# DAC_40MHz.net
KiCad netlist of a schematic drawn in Altium Designer
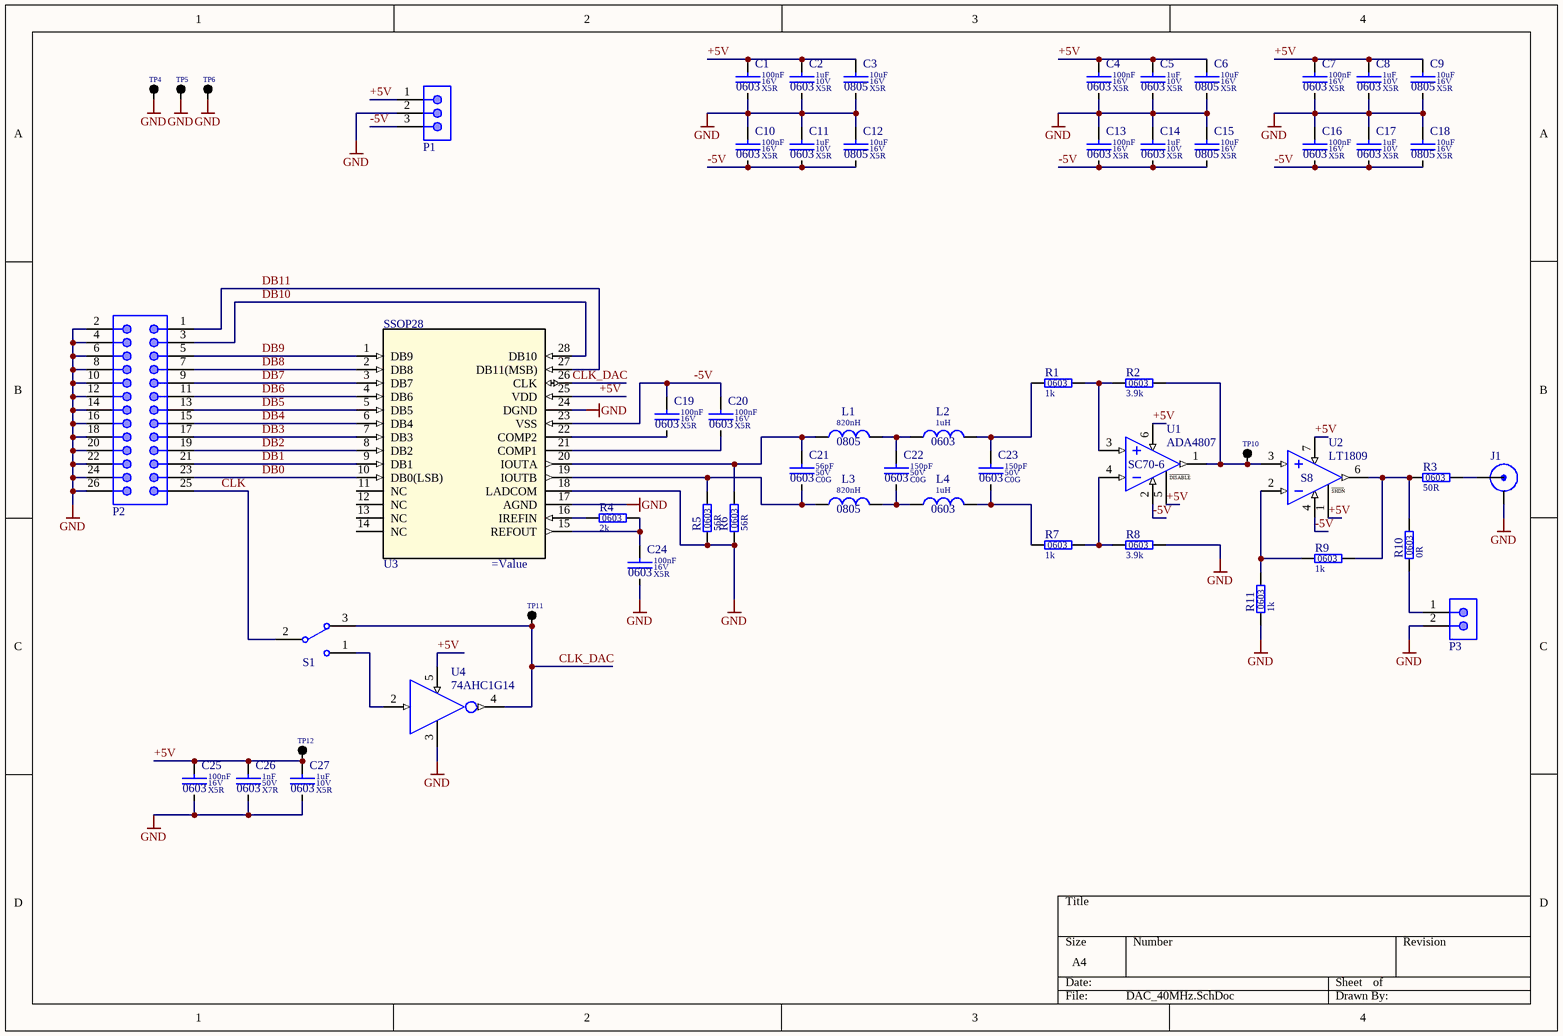
[diagram p0: DAC_40MHz.SchDoc]

(export (version "E")
  (design (tool "Eeschema 10.0.6"))
  (components
    (comp (ref "C1")
      (value "100nF")
      (footprint "C_0603")
      (description "Capacitor")
      (fields
        (field (name "DIELECTRIC") "X5R")
        (field (name "VOLTAGE") "16V")
        (field (name "SCH_FOOTPRINT") "0603")
        (field (name "PART NUMBER") "C_100nF_16V_X5R_0603_10")
        (field (name "TOLERANCE") "10%")
      )
      (libsource (lib "MatyczLib") (part "C"))
    )
    (comp (ref "C2")
      (value "1uF")
      (footprint "C_0603")
      (description "Capacitor")
      (fields
        (field (name "DIELECTRIC") "X5R")
        (field (name "VOLTAGE") "10V")
        (field (name "SCH_FOOTPRINT") "0603")
        (field (name "PART NUMBER") "C_1uF_10V_X5R_0603_10")
        (field (name "TOLERANCE") "10%")
      )
      (libsource (lib "MatyczLib") (part "C"))
    )
    (comp (ref "C3")
      (value "10uF")
      (footprint "C_0805")
      (description "Capacitor")
      (fields
        (field (name "DIELECTRIC") "X5R")
        (field (name "VOLTAGE") "16V")
        (field (name "SCH_FOOTPRINT") "0805")
        (field (name "PART NUMBER") "C_10uF_16V_X5R_0805_10")
        (field (name "TOLERANCE") "10%")
      )
      (libsource (lib "MatyczLib") (part "C"))
    )
    (comp (ref "C4")
      (value "100nF")
      (footprint "C_0603")
      (description "Capacitor")
      (fields
        (field (name "DIELECTRIC") "X5R")
        (field (name "VOLTAGE") "16V")
        (field (name "SCH_FOOTPRINT") "0603")
        (field (name "PART NUMBER") "C_100nF_16V_X5R_0603_10")
        (field (name "TOLERANCE") "10%")
      )
      (libsource (lib "MatyczLib") (part "C"))
    )
    (comp (ref "C5")
      (value "1uF")
      (footprint "C_0603")
      (description "Capacitor")
      (fields
        (field (name "DIELECTRIC") "X5R")
        (field (name "VOLTAGE") "10V")
        (field (name "SCH_FOOTPRINT") "0603")
        (field (name "PART NUMBER") "C_1uF_10V_X5R_0603_10")
        (field (name "TOLERANCE") "10%")
      )
      (libsource (lib "MatyczLib") (part "C"))
    )
    (comp (ref "C6")
      (value "10uF")
      (footprint "C_0805")
      (description "Capacitor")
      (fields
        (field (name "DIELECTRIC") "X5R")
        (field (name "VOLTAGE") "16V")
        (field (name "SCH_FOOTPRINT") "0805")
        (field (name "PART NUMBER") "C_10uF_16V_X5R_0805_10")
        (field (name "TOLERANCE") "10%")
      )
      (libsource (lib "MatyczLib") (part "C"))
    )
    (comp (ref "C7")
      (value "100nF")
      (footprint "C_0603")
      (description "Capacitor")
      (fields
        (field (name "DIELECTRIC") "X5R")
        (field (name "VOLTAGE") "16V")
        (field (name "SCH_FOOTPRINT") "0603")
        (field (name "PART NUMBER") "C_100nF_16V_X5R_0603_10")
        (field (name "TOLERANCE") "10%")
      )
      (libsource (lib "MatyczLib") (part "C"))
    )
    (comp (ref "C8")
      (value "1uF")
      (footprint "C_0603")
      (description "Capacitor")
      (fields
        (field (name "DIELECTRIC") "X5R")
        (field (name "VOLTAGE") "10V")
        (field (name "SCH_FOOTPRINT") "0603")
        (field (name "PART NUMBER") "C_1uF_10V_X5R_0603_10")
        (field (name "TOLERANCE") "10%")
      )
      (libsource (lib "MatyczLib") (part "C"))
    )
    (comp (ref "C9")
      (value "10uF")
      (footprint "C_0805")
      (description "Capacitor")
      (fields
        (field (name "DIELECTRIC") "X5R")
        (field (name "VOLTAGE") "16V")
        (field (name "SCH_FOOTPRINT") "0805")
        (field (name "PART NUMBER") "C_10uF_16V_X5R_0805_10")
        (field (name "TOLERANCE") "10%")
      )
      (libsource (lib "MatyczLib") (part "C"))
    )
    (comp (ref "C10")
      (value "100nF")
      (footprint "C_0603")
      (description "Capacitor")
      (fields
        (field (name "DIELECTRIC") "X5R")
        (field (name "VOLTAGE") "16V")
        (field (name "SCH_FOOTPRINT") "0603")
        (field (name "PART NUMBER") "C_100nF_16V_X5R_0603_10")
        (field (name "TOLERANCE") "10%")
      )
      (libsource (lib "MatyczLib") (part "C"))
    )
    (comp (ref "C11")
      (value "1uF")
      (footprint "C_0603")
      (description "Capacitor")
      (fields
        (field (name "DIELECTRIC") "X5R")
        (field (name "VOLTAGE") "10V")
        (field (name "SCH_FOOTPRINT") "0603")
        (field (name "PART NUMBER") "C_1uF_10V_X5R_0603_10")
        (field (name "TOLERANCE") "10%")
      )
      (libsource (lib "MatyczLib") (part "C"))
    )
    (comp (ref "C12")
      (value "10uF")
      (footprint "C_0805")
      (description "Capacitor")
      (fields
        (field (name "DIELECTRIC") "X5R")
        (field (name "VOLTAGE") "16V")
        (field (name "SCH_FOOTPRINT") "0805")
        (field (name "PART NUMBER") "C_10uF_16V_X5R_0805_10")
        (field (name "TOLERANCE") "10%")
      )
      (libsource (lib "MatyczLib") (part "C"))
    )
    (comp (ref "C13")
      (value "100nF")
      (footprint "C_0603")
      (description "Capacitor")
      (fields
        (field (name "DIELECTRIC") "X5R")
        (field (name "VOLTAGE") "16V")
        (field (name "SCH_FOOTPRINT") "0603")
        (field (name "PART NUMBER") "C_100nF_16V_X5R_0603_10")
        (field (name "TOLERANCE") "10%")
      )
      (libsource (lib "MatyczLib") (part "C"))
    )
    (comp (ref "C14")
      (value "1uF")
      (footprint "C_0603")
      (description "Capacitor")
      (fields
        (field (name "DIELECTRIC") "X5R")
        (field (name "VOLTAGE") "10V")
        (field (name "SCH_FOOTPRINT") "0603")
        (field (name "PART NUMBER") "C_1uF_10V_X5R_0603_10")
        (field (name "TOLERANCE") "10%")
      )
      (libsource (lib "MatyczLib") (part "C"))
    )
    (comp (ref "C15")
      (value "10uF")
      (footprint "C_0805")
      (description "Capacitor")
      (fields
        (field (name "DIELECTRIC") "X5R")
        (field (name "VOLTAGE") "16V")
        (field (name "SCH_FOOTPRINT") "0805")
        (field (name "PART NUMBER") "C_10uF_16V_X5R_0805_10")
        (field (name "TOLERANCE") "10%")
      )
      (libsource (lib "MatyczLib") (part "C"))
    )
    (comp (ref "C16")
      (value "100nF")
      (footprint "C_0603")
      (description "Capacitor")
      (fields
        (field (name "DIELECTRIC") "X5R")
        (field (name "VOLTAGE") "16V")
        (field (name "SCH_FOOTPRINT") "0603")
        (field (name "PART NUMBER") "C_100nF_16V_X5R_0603_10")
        (field (name "TOLERANCE") "10%")
      )
      (libsource (lib "MatyczLib") (part "C"))
    )
    (comp (ref "C17")
      (value "1uF")
      (footprint "C_0603")
      (description "Capacitor")
      (fields
        (field (name "DIELECTRIC") "X5R")
        (field (name "VOLTAGE") "10V")
        (field (name "SCH_FOOTPRINT") "0603")
        (field (name "PART NUMBER") "C_1uF_10V_X5R_0603_10")
        (field (name "TOLERANCE") "10%")
      )
      (libsource (lib "MatyczLib") (part "C"))
    )
    (comp (ref "C18")
      (value "10uF")
      (footprint "C_0805")
      (description "Capacitor")
      (fields
        (field (name "DIELECTRIC") "X5R")
        (field (name "VOLTAGE") "16V")
        (field (name "SCH_FOOTPRINT") "0805")
        (field (name "PART NUMBER") "C_10uF_16V_X5R_0805_10")
        (field (name "TOLERANCE") "10%")
      )
      (libsource (lib "MatyczLib") (part "C"))
    )
    (comp (ref "C19")
      (value "100nF")
      (footprint "C_0603")
      (description "Capacitor")
      (fields
        (field (name "DIELECTRIC") "X5R")
        (field (name "VOLTAGE") "16V")
        (field (name "SCH_FOOTPRINT") "0603")
        (field (name "PART NUMBER") "C_100nF_16V_X5R_0603_10")
        (field (name "TOLERANCE") "10%")
      )
      (libsource (lib "MatyczLib") (part "C"))
    )
    (comp (ref "C20")
      (value "100nF")
      (footprint "C_0603")
      (description "Capacitor")
      (fields
        (field (name "DIELECTRIC") "X5R")
        (field (name "VOLTAGE") "16V")
        (field (name "SCH_FOOTPRINT") "0603")
        (field (name "PART NUMBER") "C_100nF_16V_X5R_0603_10")
        (field (name "TOLERANCE") "10%")
      )
      (libsource (lib "MatyczLib") (part "C"))
    )
    (comp (ref "C21")
      (value "56pF")
      (footprint "C_0603")
      (description "Capacitor")
      (fields
        (field (name "DIELECTRIC") "C0G")
        (field (name "VOLTAGE") "50V")
        (field (name "SCH_FOOTPRINT") "0603")
        (field (name "PART NUMBER") "C_56pF_50V_C0G_0603_5")
        (field (name "TOLERANCE") "5%")
      )
      (libsource (lib "MatyczLib") (part "C"))
    )
    (comp (ref "C22")
      (value "150pF")
      (footprint "C_0603")
      (description "Capacitor")
      (fields
        (field (name "DIELECTRIC") "C0G")
        (field (name "VOLTAGE") "50V")
        (field (name "SCH_FOOTPRINT") "0603")
        (field (name "PART NUMBER") "C_150pF_50V_C0G_0603_5")
        (field (name "TOLERANCE") "5%")
      )
      (libsource (lib "MatyczLib") (part "C"))
    )
    (comp (ref "C23")
      (value "150pF")
      (footprint "C_0603")
      (description "Capacitor")
      (fields
        (field (name "DIELECTRIC") "C0G")
        (field (name "VOLTAGE") "50V")
        (field (name "SCH_FOOTPRINT") "0603")
        (field (name "PART NUMBER") "C_150pF_50V_C0G_0603_5")
        (field (name "TOLERANCE") "5%")
      )
      (libsource (lib "MatyczLib") (part "C"))
    )
    (comp (ref "C24")
      (value "100nF")
      (footprint "C_0603")
      (description "Capacitor")
      (fields
        (field (name "DIELECTRIC") "X5R")
        (field (name "VOLTAGE") "16V")
        (field (name "SCH_FOOTPRINT") "0603")
        (field (name "PART NUMBER") "C_100nF_16V_X5R_0603_10")
        (field (name "TOLERANCE") "10%")
      )
      (libsource (lib "MatyczLib") (part "C"))
    )
    (comp (ref "C25")
      (value "100nF")
      (footprint "C_0603")
      (description "Capacitor")
      (fields
        (field (name "DIELECTRIC") "X5R")
        (field (name "VOLTAGE") "16V")
        (field (name "SCH_FOOTPRINT") "0603")
        (field (name "PART NUMBER") "C_100nF_16V_X5R_0603_10")
        (field (name "TOLERANCE") "10%")
      )
      (libsource (lib "MatyczLib") (part "C"))
    )
    (comp (ref "C26")
      (value "1nF")
      (footprint "C_0603")
      (description "Capacitor")
      (fields
        (field (name "DIELECTRIC") "X7R")
        (field (name "VOLTAGE") "50V")
        (field (name "SCH_FOOTPRINT") "0603")
        (field (name "PART NUMBER") "C_1nF_50V_X7R_0603_10")
        (field (name "TOLERANCE") "10%")
      )
      (libsource (lib "MatyczLib") (part "C"))
    )
    (comp (ref "C27")
      (value "1uF")
      (footprint "C_0603")
      (description "Capacitor")
      (fields
        (field (name "DIELECTRIC") "X5R")
        (field (name "VOLTAGE") "10V")
        (field (name "SCH_FOOTPRINT") "0603")
        (field (name "PART NUMBER") "C_1uF_10V_X5R_0603_10")
        (field (name "TOLERANCE") "10%")
      )
      (libsource (lib "MatyczLib") (part "C"))
    )
    (comp (ref "J1")
      (value "SMA vertical connector")
      (footprint "J_SMA_VERTICAL")
      (fields (field (name "PART NUMBER") "J_SMA_VERTICAL"))
      (libsource (lib "MatyczLib") (part "J_SMA_VERTICAL"))
    )
    (comp (ref "L1")
      (value "820nH")
      (footprint "L_0805")
      (description "Induction")
      (fields
        (field (name "SCH_FOOTPRINT") "0805")
        (field (name "PART NUMBER") "L_820nH_180mA_0805")
        (field (name "MANUFACTURER") "MULTICOMP")
      )
      (libsource (lib "MatyczLib") (part "L"))
    )
    (comp (ref "L2")
      (value "1uH")
      (footprint "L_0603")
      (description "Induction")
      (fields
        (field (name "SCH_FOOTPRINT") "0603")
        (field (name "PART NUMBER") "L_1uH_100mA_0603")
        (field (name "MANUFACTURER") "BOURNS")
      )
      (libsource (lib "MatyczLib") (part "L"))
    )
    (comp (ref "L3")
      (value "820nH")
      (footprint "L_0805")
      (description "Induction")
      (fields
        (field (name "SCH_FOOTPRINT") "0805")
        (field (name "PART NUMBER") "L_820nH_180mA_0805")
        (field (name "MANUFACTURER") "MULTICOMP")
      )
      (libsource (lib "MatyczLib") (part "L"))
    )
    (comp (ref "L4")
      (value "1uH")
      (footprint "L_0603")
      (description "Induction")
      (fields
        (field (name "SCH_FOOTPRINT") "0603")
        (field (name "PART NUMBER") "L_1uH_100mA_0603")
        (field (name "MANUFACTURER") "BOURNS")
      )
      (libsource (lib "MatyczLib") (part "L"))
    )
    (comp (ref "P1")
      (value "Header 1x3, THT, 2,54mm")
      (footprint "P_HEADER_1x3_THT_2.54_VERT")
      (description "Pin Header, THT, pitch 2.54mm, Single Row, Vertical, 3pin")
      (fields (field (name "PART NUMBER") "P_HEADER_1x3_THT_2.54_VERT"))
      (libsource (lib "MatyczLib") (part "P_HEADER_1x3_THT_2.54_VERT"))
    )
    (comp (ref "P2")
      (value "Header 2x13, THT, 2,54mm")
      (footprint "P_HEADER_2x13_THT_2.54_VERT")
      (description "Pin Header, THT, pitch 2.54mm, Dual Row, Vertical, 26pin")
      (fields (field (name "PART NUMBER") "P_HEADER_2x13_THT_2.54_VERT"))
      (libsource (lib "MatyczLib") (part "P_HEADER_2x13_THT_2.54_VERT"))
    )
    (comp (ref "P3")
      (value "Header 1x2, THT, 2,54mm")
      (footprint "P_HEADER_1x2_THT_2.54_VERT")
      (description "Pin Header, THT, pitch 2.54mm, Single Row, Vertical, 2pin")
      (fields (field (name "PART NUMBER") "P_HEADER_1x2_THT_2.54_VERT"))
      (libsource (lib "MatyczLib") (part "P_HEADER_1x2_THT_2.54_VERT"))
    )
    (comp (ref "R1")
      (value "1k")
      (footprint "R_0603")
      (fields
        (field (name "SCH_FOOTPRINT") "0603")
        (field (name "PART NUMBER") "R_1k_0603_1")
        (field (name "TOLERANCE") "1%")
        (field (name "POWER") "100mW")
      )
      (libsource (lib "MatyczLib") (part "R"))
    )
    (comp (ref "R2")
      (value "3.9k")
      (footprint "R_0603")
      (fields
        (field (name "SCH_FOOTPRINT") "0603")
        (field (name "PART NUMBER") "R_3.9k_0603_1")
        (field (name "TOLERANCE") "1%")
        (field (name "POWER") "100mW")
      )
      (libsource (lib "MatyczLib") (part "R"))
    )
    (comp (ref "R3")
      (value "50R")
      (footprint "R_0603")
      (fields
        (field (name "SCH_FOOTPRINT") "0603")
        (field (name "PART NUMBER") "R_50R_0603_1")
        (field (name "TOLERANCE") "1%")
        (field (name "POWER") "100mW")
      )
      (libsource (lib "MatyczLib") (part "R"))
    )
    (comp (ref "R4")
      (value "2k")
      (footprint "R_0603")
      (fields
        (field (name "SCH_FOOTPRINT") "0603")
        (field (name "PART NUMBER") "R_2k_0603_1")
        (field (name "TOLERANCE") "1%")
        (field (name "POWER") "100mW")
      )
      (libsource (lib "MatyczLib") (part "R"))
    )
    (comp (ref "R5")
      (value "56R")
      (footprint "R_0603")
      (fields
        (field (name "SCH_FOOTPRINT") "0603")
        (field (name "PART NUMBER") "R_56R_0603_1")
        (field (name "TOLERANCE") "1%")
        (field (name "POWER") "100mW")
      )
      (libsource (lib "") (part "R_1"))
    )
    (comp (ref "R6")
      (value "56R")
      (footprint "R_0603")
      (fields
        (field (name "SCH_FOOTPRINT") "0603")
        (field (name "PART NUMBER") "R_56R_0603_1")
        (field (name "TOLERANCE") "1%")
        (field (name "POWER") "100mW")
      )
      (libsource (lib "") (part "R_1"))
    )
    (comp (ref "R7")
      (value "1k")
      (footprint "R_0603")
      (fields
        (field (name "SCH_FOOTPRINT") "0603")
        (field (name "PART NUMBER") "R_1k_0603_1")
        (field (name "TOLERANCE") "1%")
        (field (name "POWER") "100mW")
      )
      (libsource (lib "MatyczLib") (part "R"))
    )
    (comp (ref "R8")
      (value "3.9k")
      (footprint "R_0603")
      (fields
        (field (name "SCH_FOOTPRINT") "0603")
        (field (name "PART NUMBER") "R_3.9k_0603_1")
        (field (name "TOLERANCE") "1%")
        (field (name "POWER") "100mW")
      )
      (libsource (lib "MatyczLib") (part "R"))
    )
    (comp (ref "R9")
      (value "1k")
      (footprint "R_0603")
      (fields
        (field (name "SCH_FOOTPRINT") "0603")
        (field (name "PART NUMBER") "R_1k_0603_1")
        (field (name "TOLERANCE") "1%")
        (field (name "POWER") "100mW")
      )
      (libsource (lib "MatyczLib") (part "R"))
    )
    (comp (ref "R10")
      (value "0R")
      (footprint "R_0603")
      (fields
        (field (name "SCH_FOOTPRINT") "0603")
        (field (name "PART NUMBER") "R_0R_0603_1")
        (field (name "TOLERANCE") "1%")
        (field (name "POWER") "100mW")
      )
      (libsource (lib "") (part "R_1"))
    )
    (comp (ref "R11")
      (value "1k")
      (footprint "R_0603")
      (fields
        (field (name "SCH_FOOTPRINT") "0603")
        (field (name "PART NUMBER") "R_1k_0603_1")
        (field (name "TOLERANCE") "1%")
        (field (name "POWER") "100mW")
      )
      (libsource (lib "") (part "R_1"))
    )
    (comp (ref "S1")
      (value "Single Pole Double Throw Slideswitch")
      (footprint "S_SLIDESWITCH_SPDT")
      (fields
        (field (name "PART NUMBER") "S_SLIDESWITCH_SPDT_OS102011MS2QN1")
        (field (name "MANUFACTURER PART NUMBER") "OS102011MS2QN13")
      )
      (libsource (lib "MatyczLib") (part "S_SPDT"))
    )
    (comp (ref "TP4")
      (value "Single pin")
      (footprint "TP_1PIN")
      (description "Testpoint")
      (fields (field (name "PART NUMBER") "TP_1PIN"))
      (libsource (lib "Library") (part "TP_TESTPOINT"))
    )
    (comp (ref "TP5")
      (value "Single pin")
      (footprint "TP_1PIN")
      (description "Testpoint")
      (fields (field (name "PART NUMBER") "TP_1PIN"))
      (libsource (lib "Library") (part "TP_TESTPOINT"))
    )
    (comp (ref "TP6")
      (value "Single pin")
      (footprint "TP_1PIN")
      (description "Testpoint")
      (fields (field (name "PART NUMBER") "TP_1PIN"))
      (libsource (lib "Library") (part "TP_TESTPOINT"))
    )
    (comp (ref "TP10")
      (value "Single pin")
      (footprint "TP_1PIN")
      (description "Testpoint")
      (fields (field (name "PART NUMBER") "TP_1PIN"))
      (libsource (lib "Library") (part "TP_TESTPOINT"))
    )
    (comp (ref "TP11")
      (value "Single pin")
      (footprint "TP_1PIN")
      (description "Testpoint")
      (fields (field (name "PART NUMBER") "TP_1PIN"))
      (libsource (lib "Library") (part "TP_TESTPOINT"))
    )
    (comp (ref "TP12")
      (value "Single pin")
      (footprint "TP_1PIN")
      (description "Testpoint")
      (fields (field (name "PART NUMBER") "TP_1PIN"))
      (libsource (lib "Library") (part "TP_TESTPOINT"))
    )
    (comp (ref "U1")
      (value "ADA4807")
      (footprint "SC70-6_TSSOP6_2X1.25_MD")
      (fields
        (field (name "SCH_FOOTPRINT") "SC70-6")
        (field (name "PART NUMBER") "U_ADA4807-1AKSZ-R2")
        (field (name "MANUFACTURER") "ANALOG DEVICES")
      )
      (libsource (lib "MatyczLib") (part "U_ADA4807"))
    )
    (comp (ref "U2")
      (value "LT1809")
      (footprint "S8_SOP8_SOIC8_SO8_4.9X3.9_MD")
      (fields
        (field (name "SCH_FOOTPRINT") "S8")
        (field (name "PART NUMBER") "U_LT1809CS8")
        (field (name "MANUFACTURER") "ANALOG DEVICES")
      )
      (libsource (lib "MatyczLib") (part "U_LT1809"))
    )
    (comp (ref "U3")
      (value "~")
      (footprint "SSOP28_SOP28_SO28_SOIC8_10.2X5.29_MD")
      (description "12-bit 50Msps DAC")
      (fields
        (field (name "SCH_FOOTPRINT") "SSOP28")
        (field (name "PART NUMBER") "U_LTC1666")
        (field (name "MANUFACTURER PART NUMBER") "LTC1666")
      )
      (libsource (lib "MatyczLib") (part "U_LTC1666"))
    )
    (comp (ref "U4")
      (value "74AHC1G14")
      (footprint "SOT23-5_2.05X2.13_MD")
      (description "Inverting Schmitt trigger")
      (fields (field (name "PART NUMBER") "U_74AHC1G14") (field (name "MANUFACTURER") "NEXPERIA"))
      (libsource (lib "MatyczLib") (part "U_SCHMITT_INVERTER"))
    )
  )
  (nets
    (net (code "1") (name "/+5V") (class "Default")
      (node (ref "C1") (pin "1") (pinfunction "1_1") (pintype "passive"))
      (node (ref "C2") (pin "1") (pinfunction "1_1") (pintype "passive"))
      (node (ref "C25") (pin "1") (pinfunction "1_1") (pintype "passive"))
      (node (ref "C26") (pin "1") (pinfunction "1_1") (pintype "passive"))
      (node (ref "C27") (pin "1") (pinfunction "1_1") (pintype "passive"))
      (node (ref "C3") (pin "1") (pinfunction "1_1") (pintype "passive"))
      (node (ref "C4") (pin "1") (pinfunction "1_1") (pintype "passive"))
      (node (ref "C5") (pin "1") (pinfunction "1_1") (pintype "passive"))
      (node (ref "C6") (pin "1") (pinfunction "1_1") (pintype "passive"))
      (node (ref "C7") (pin "1") (pinfunction "1_1") (pintype "passive"))
      (node (ref "C8") (pin "1") (pinfunction "1_1") (pintype "passive"))
      (node (ref "C9") (pin "1") (pinfunction "1_1") (pintype "passive"))
      (node (ref "P1") (pin "1") (pinfunction "1_1") (pintype "passive"))
      (node (ref "TP12") (pin "1") (pinfunction "TP_1") (pintype "passive"))
      (node (ref "U1") (pin "5") (pinfunction "~{DISABL}E_5") (pintype "passive"))
      (node (ref "U1") (pin "6") (pinfunction "Vs+_6") (pintype "input"))
      (node (ref "U2") (pin "1") (pinfunction "~{SHD}N_1") (pintype "passive"))
      (node (ref "U2") (pin "7") (pinfunction "Vs+_7") (pintype "input"))
      (node (ref "U3") (pin "25") (pinfunction "VDD_25") (pintype "input"))
      (node (ref "U4") (pin "5") (pinfunction "Vcc_5") (pintype "input"))
    )
    (net (code "2") (name "/-5V") (class "Default")
      (node (ref "C10") (pin "2") (pinfunction "2_2") (pintype "passive"))
      (node (ref "C11") (pin "2") (pinfunction "2_2") (pintype "passive"))
      (node (ref "C12") (pin "2") (pinfunction "2_2") (pintype "passive"))
      (node (ref "C13") (pin "2") (pinfunction "2_2") (pintype "passive"))
      (node (ref "C14") (pin "2") (pinfunction "2_2") (pintype "passive"))
      (node (ref "C15") (pin "2") (pinfunction "2_2") (pintype "passive"))
      (node (ref "C16") (pin "2") (pinfunction "2_2") (pintype "passive"))
      (node (ref "C17") (pin "2") (pinfunction "2_2") (pintype "passive"))
      (node (ref "C18") (pin "2") (pinfunction "2_2") (pintype "passive"))
      (node (ref "C19") (pin "1") (pinfunction "1_1") (pintype "passive"))
      (node (ref "C20") (pin "1") (pinfunction "1_1") (pintype "passive"))
      (node (ref "P1") (pin "3") (pinfunction "3_3") (pintype "passive"))
      (node (ref "U1") (pin "2") (pinfunction "Vs-_2") (pintype "input"))
      (node (ref "U2") (pin "4") (pinfunction "Vs-_4") (pintype "input"))
      (node (ref "U3") (pin "23") (pinfunction "VSS_23") (pintype "input"))
    )
    (net (code "3") (name "/CLK") (class "Default")
      (node (ref "P2") (pin "25") (pinfunction "25_25") (pintype "passive"))
      (node (ref "S1") (pin "2") (pinfunction "2_2") (pintype "passive"))
    )
    (net (code "4") (name "/CLK_DAC") (class "Default")
      (node (ref "S1") (pin "3") (pinfunction "3_3") (pintype "passive"))
      (node (ref "TP11") (pin "1") (pinfunction "TP_1") (pintype "passive"))
      (node (ref "U3") (pin "26") (pinfunction "CLK_26") (pintype "bidirectional"))
      (node (ref "U4") (pin "4") (pinfunction "OUT_4") (pintype "output"))
    )
    (net (code "5") (name "/DB0") (class "Default")
      (node (ref "P2") (pin "23") (pinfunction "23_23") (pintype "passive"))
      (node (ref "U3") (pin "10") (pinfunction "DB0(LSB)_10") (pintype "input"))
    )
    (net (code "6") (name "/DB1") (class "Default")
      (node (ref "P2") (pin "21") (pinfunction "21_21") (pintype "passive"))
      (node (ref "U3") (pin "9") (pinfunction "DB1_9") (pintype "input"))
    )
    (net (code "7") (name "/DB2") (class "Default")
      (node (ref "P2") (pin "19") (pinfunction "19_19") (pintype "passive"))
      (node (ref "U3") (pin "8") (pinfunction "DB2_8") (pintype "input"))
    )
    (net (code "8") (name "/DB3") (class "Default")
      (node (ref "P2") (pin "17") (pinfunction "17_17") (pintype "passive"))
      (node (ref "U3") (pin "7") (pinfunction "DB3_7") (pintype "input"))
    )
    (net (code "9") (name "/DB4") (class "Default")
      (node (ref "P2") (pin "15") (pinfunction "15_15") (pintype "passive"))
      (node (ref "U3") (pin "6") (pinfunction "DB4_6") (pintype "input"))
    )
    (net (code "10") (name "/DB5") (class "Default")
      (node (ref "P2") (pin "13") (pinfunction "13_13") (pintype "passive"))
      (node (ref "U3") (pin "5") (pinfunction "DB5_5") (pintype "input"))
    )
    (net (code "11") (name "/DB6") (class "Default")
      (node (ref "P2") (pin "11") (pinfunction "11_11") (pintype "passive"))
      (node (ref "U3") (pin "4") (pinfunction "DB6_4") (pintype "input"))
    )
    (net (code "12") (name "/DB7") (class "Default")
      (node (ref "P2") (pin "9") (pinfunction "9_9") (pintype "passive"))
      (node (ref "U3") (pin "3") (pinfunction "DB7_3") (pintype "input"))
    )
    (net (code "13") (name "/DB8") (class "Default")
      (node (ref "P2") (pin "7") (pinfunction "7_7") (pintype "passive"))
      (node (ref "U3") (pin "2") (pinfunction "DB8_2") (pintype "input"))
    )
    (net (code "14") (name "/DB9") (class "Default")
      (node (ref "P2") (pin "5") (pinfunction "5_5") (pintype "passive"))
      (node (ref "U3") (pin "1") (pinfunction "DB9_1") (pintype "input"))
    )
    (net (code "15") (name "/DB10") (class "Default")
      (node (ref "P2") (pin "3") (pinfunction "3_3") (pintype "passive"))
      (node (ref "U3") (pin "28") (pinfunction "DB10_28") (pintype "input"))
    )
    (net (code "16") (name "/DB11") (class "Default")
      (node (ref "P2") (pin "1") (pinfunction "1_1") (pintype "passive"))
      (node (ref "U3") (pin "27") (pinfunction "DB11(MSB)_27") (pintype "input"))
    )
    (net (code "17") (name "GND") (class "Default")
      (node (ref "C1") (pin "2") (pinfunction "2_2") (pintype "passive"))
      (node (ref "C10") (pin "1") (pinfunction "1_1") (pintype "passive"))
      (node (ref "C11") (pin "1") (pinfunction "1_1") (pintype "passive"))
      (node (ref "C12") (pin "1") (pinfunction "1_1") (pintype "passive"))
      (node (ref "C13") (pin "1") (pinfunction "1_1") (pintype "passive"))
      (node (ref "C14") (pin "1") (pinfunction "1_1") (pintype "passive"))
      (node (ref "C15") (pin "1") (pinfunction "1_1") (pintype "passive"))
      (node (ref "C16") (pin "1") (pinfunction "1_1") (pintype "passive"))
      (node (ref "C17") (pin "1") (pinfunction "1_1") (pintype "passive"))
      (node (ref "C18") (pin "1") (pinfunction "1_1") (pintype "passive"))
      (node (ref "C2") (pin "2") (pinfunction "2_2") (pintype "passive"))
      (node (ref "C24") (pin "2") (pinfunction "2_2") (pintype "passive"))
      (node (ref "C25") (pin "2") (pinfunction "2_2") (pintype "passive"))
      (node (ref "C26") (pin "2") (pinfunction "2_2") (pintype "passive"))
      (node (ref "C27") (pin "2") (pinfunction "2_2") (pintype "passive"))
      (node (ref "C3") (pin "2") (pinfunction "2_2") (pintype "passive"))
      (node (ref "C4") (pin "2") (pinfunction "2_2") (pintype "passive"))
      (node (ref "C5") (pin "2") (pinfunction "2_2") (pintype "passive"))
      (node (ref "C6") (pin "2") (pinfunction "2_2") (pintype "passive"))
      (node (ref "C7") (pin "2") (pinfunction "2_2") (pintype "passive"))
      (node (ref "C8") (pin "2") (pinfunction "2_2") (pintype "passive"))
      (node (ref "C9") (pin "2") (pinfunction "2_2") (pintype "passive"))
      (node (ref "J1") (pin "2") (pinfunction "GND_2") (pintype "passive"))
      (node (ref "P1") (pin "2") (pinfunction "2_2") (pintype "passive"))
      (node (ref "P2") (pin "10") (pinfunction "10_10") (pintype "passive"))
      (node (ref "P2") (pin "12") (pinfunction "12_12") (pintype "passive"))
      (node (ref "P2") (pin "14") (pinfunction "14_14") (pintype "passive"))
      (node (ref "P2") (pin "16") (pinfunction "16_16") (pintype "passive"))
      (node (ref "P2") (pin "18") (pinfunction "18_18") (pintype "passive"))
      (node (ref "P2") (pin "2") (pinfunction "2_2") (pintype "passive"))
      (node (ref "P2") (pin "20") (pinfunction "20_20") (pintype "passive"))
      (node (ref "P2") (pin "22") (pinfunction "22_22") (pintype "passive"))
      (node (ref "P2") (pin "24") (pinfunction "24_24") (pintype "passive"))
      (node (ref "P2") (pin "26") (pinfunction "26_26") (pintype "passive"))
      (node (ref "P2") (pin "4") (pinfunction "4_4") (pintype "passive"))
      (node (ref "P2") (pin "6") (pinfunction "6_6") (pintype "passive"))
      (node (ref "P2") (pin "8") (pinfunction "8_8") (pintype "passive"))
      (node (ref "P3") (pin "2") (pinfunction "2_2") (pintype "passive"))
      (node (ref "R11") (pin "1") (pinfunction "1_1") (pintype "passive"))
      (node (ref "R5") (pin "1") (pinfunction "1_1") (pintype "passive"))
      (node (ref "R6") (pin "1") (pinfunction "1_1") (pintype "passive"))
      (node (ref "R8") (pin "2") (pinfunction "2_2") (pintype "passive"))
      (node (ref "TP4") (pin "1") (pinfunction "TP_1") (pintype "passive"))
      (node (ref "TP5") (pin "1") (pinfunction "TP_1") (pintype "passive"))
      (node (ref "TP6") (pin "1") (pinfunction "TP_1") (pintype "passive"))
      (node (ref "U3") (pin "17") (pinfunction "AGND_17") (pintype "power_in"))
      (node (ref "U3") (pin "18") (pinfunction "LADCOM_18") (pintype "passive"))
      (node (ref "U3") (pin "24") (pinfunction "DGND_24") (pintype "power_in"))
      (node (ref "U4") (pin "3") (pinfunction "GND_3") (pintype "power_in"))
    )
    (net (code "18") (name "Net-(C22-Pad1)") (class "Default")
      (node (ref "C22") (pin "1") (pinfunction "1_1") (pintype "passive"))
      (node (ref "L1") (pin "2") (pinfunction "2_2") (pintype "passive"))
      (node (ref "L2") (pin "1") (pinfunction "1_1") (pintype "passive"))
    )
    (net (code "19") (name "Net-(C22-Pad2)") (class "Default")
      (node (ref "C22") (pin "2") (pinfunction "2_2") (pintype "passive"))
      (node (ref "L3") (pin "2") (pinfunction "2_2") (pintype "passive"))
      (node (ref "L4") (pin "1") (pinfunction "1_1") (pintype "passive"))
    )
    (net (code "20") (name "Net-(C23-Pad1)") (class "Default")
      (node (ref "C23") (pin "1") (pinfunction "1_1") (pintype "passive"))
      (node (ref "L2") (pin "2") (pinfunction "2_2") (pintype "passive"))
      (node (ref "R1") (pin "1") (pinfunction "1_1") (pintype "passive"))
    )
    (net (code "21") (name "Net-(C23-Pad2)") (class "Default")
      (node (ref "C23") (pin "2") (pinfunction "2_2") (pintype "passive"))
      (node (ref "L4") (pin "2") (pinfunction "2_2") (pintype "passive"))
      (node (ref "R7") (pin "1") (pinfunction "1_1") (pintype "passive"))
    )
    (net (code "22") (name "Net-(J1-SIGNAL)") (class "Default")
      (node (ref "J1") (pin "1") (pinfunction "SIGNAL_1") (pintype "passive"))
      (node (ref "R3") (pin "2") (pinfunction "2_2") (pintype "passive"))
    )
    (net (code "23") (name "Net-(P3-Pad1)") (class "Default")
      (node (ref "P3") (pin "1") (pinfunction "1_1") (pintype "passive"))
      (node (ref "R10") (pin "1") (pinfunction "1_1") (pintype "passive"))
    )
    (net (code "24") (name "Net-(TP10-TP)") (class "Default")
      (node (ref "R2") (pin "2") (pinfunction "2_2") (pintype "passive"))
      (node (ref "TP10") (pin "1") (pinfunction "TP_1") (pintype "passive"))
      (node (ref "U1") (pin "1") (pinfunction "OUT_1") (pintype "output"))
      (node (ref "U2") (pin "3") (pinfunction "IN+_3") (pintype "input"))
    )
    (net (code "25") (name "Net-(U1-IN+)") (class "Default")
      (node (ref "R1") (pin "2") (pinfunction "2_2") (pintype "passive"))
      (node (ref "R2") (pin "1") (pinfunction "1_1") (pintype "passive"))
      (node (ref "U1") (pin "3") (pinfunction "IN+_3") (pintype "input"))
    )
    (net (code "26") (name "Net-(U1-IN-)") (class "Default")
      (node (ref "R7") (pin "2") (pinfunction "2_2") (pintype "passive"))
      (node (ref "R8") (pin "1") (pinfunction "1_1") (pintype "passive"))
      (node (ref "U1") (pin "4") (pinfunction "IN-_4") (pintype "input"))
    )
    (net (code "27") (name "Net-(U2-IN-)") (class "Default")
      (node (ref "R11") (pin "2") (pinfunction "2_2") (pintype "passive"))
      (node (ref "R9") (pin "1") (pinfunction "1_1") (pintype "passive"))
      (node (ref "U2") (pin "2") (pinfunction "IN-_2") (pintype "input"))
    )
    (net (code "28") (name "Net-(U2-OUT)") (class "Default")
      (node (ref "R10") (pin "2") (pinfunction "2_2") (pintype "passive"))
      (node (ref "R3") (pin "1") (pinfunction "1_1") (pintype "passive"))
      (node (ref "R9") (pin "2") (pinfunction "2_2") (pintype "passive"))
      (node (ref "U2") (pin "6") (pinfunction "OUT_6") (pintype "output"))
    )
    (net (code "29") (name "Net-(U3-COMP1)") (class "Default")
      (node (ref "C20") (pin "2") (pinfunction "2_2") (pintype "passive"))
      (node (ref "U3") (pin "21") (pinfunction "COMP1_21") (pintype "passive"))
    )
    (net (code "30") (name "Net-(U3-COMP2)") (class "Default")
      (node (ref "C19") (pin "2") (pinfunction "2_2") (pintype "passive"))
      (node (ref "U3") (pin "22") (pinfunction "COMP2_22") (pintype "passive"))
    )
    (net (code "31") (name "Net-(U3-IOUTA)") (class "Default")
      (node (ref "C21") (pin "1") (pinfunction "1_1") (pintype "passive"))
      (node (ref "L1") (pin "1") (pinfunction "1_1") (pintype "passive"))
      (node (ref "R6") (pin "2") (pinfunction "2_2") (pintype "passive"))
      (node (ref "U3") (pin "20") (pinfunction "IOUTA_20") (pintype "output"))
    )
    (net (code "32") (name "Net-(U3-IOUTB)") (class "Default")
      (node (ref "C21") (pin "2") (pinfunction "2_2") (pintype "passive"))
      (node (ref "L3") (pin "1") (pinfunction "1_1") (pintype "passive"))
      (node (ref "R5") (pin "2") (pinfunction "2_2") (pintype "passive"))
      (node (ref "U3") (pin "19") (pinfunction "IOUTB_19") (pintype "output"))
    )
    (net (code "33") (name "Net-(U3-IREFIN)") (class "Default")
      (node (ref "R4") (pin "1") (pinfunction "1_1") (pintype "passive"))
      (node (ref "U3") (pin "16") (pinfunction "IREFIN_16") (pintype "input"))
    )
    (net (code "34") (name "Net-(U3-REFOUT)") (class "Default")
      (node (ref "C24") (pin "1") (pinfunction "1_1") (pintype "passive"))
      (node (ref "R4") (pin "2") (pinfunction "2_2") (pintype "passive"))
      (node (ref "U3") (pin "15") (pinfunction "REFOUT_15") (pintype "output"))
    )
    (net (code "35") (name "Net-(U4-A)") (class "Default")
      (node (ref "S1") (pin "1") (pinfunction "1_1") (pintype "passive"))
      (node (ref "U4") (pin "2") (pinfunction "A_2") (pintype "input"))
    )
    (net (code "36") (name "unconnected-(U3-NC-Pad11)") (class "Default")
      (node (ref "U3") (pin "11") (pinfunction "NC_11") (pintype "passive"))
    )
    (net (code "37") (name "unconnected-(U3-NC-Pad12)") (class "Default")
      (node (ref "U3") (pin "12") (pinfunction "NC_12") (pintype "passive"))
    )
    (net (code "38") (name "unconnected-(U3-NC-Pad13)") (class "Default")
      (node (ref "U3") (pin "13") (pinfunction "NC_13") (pintype "passive"))
    )
    (net (code "39") (name "unconnected-(U3-NC-Pad14)") (class "Default")
      (node (ref "U3") (pin "14") (pinfunction "NC_14") (pintype "passive"))
    )
  )
)
